# Impedance.net
KiCad netlist of a schematic drawn in EAGLE
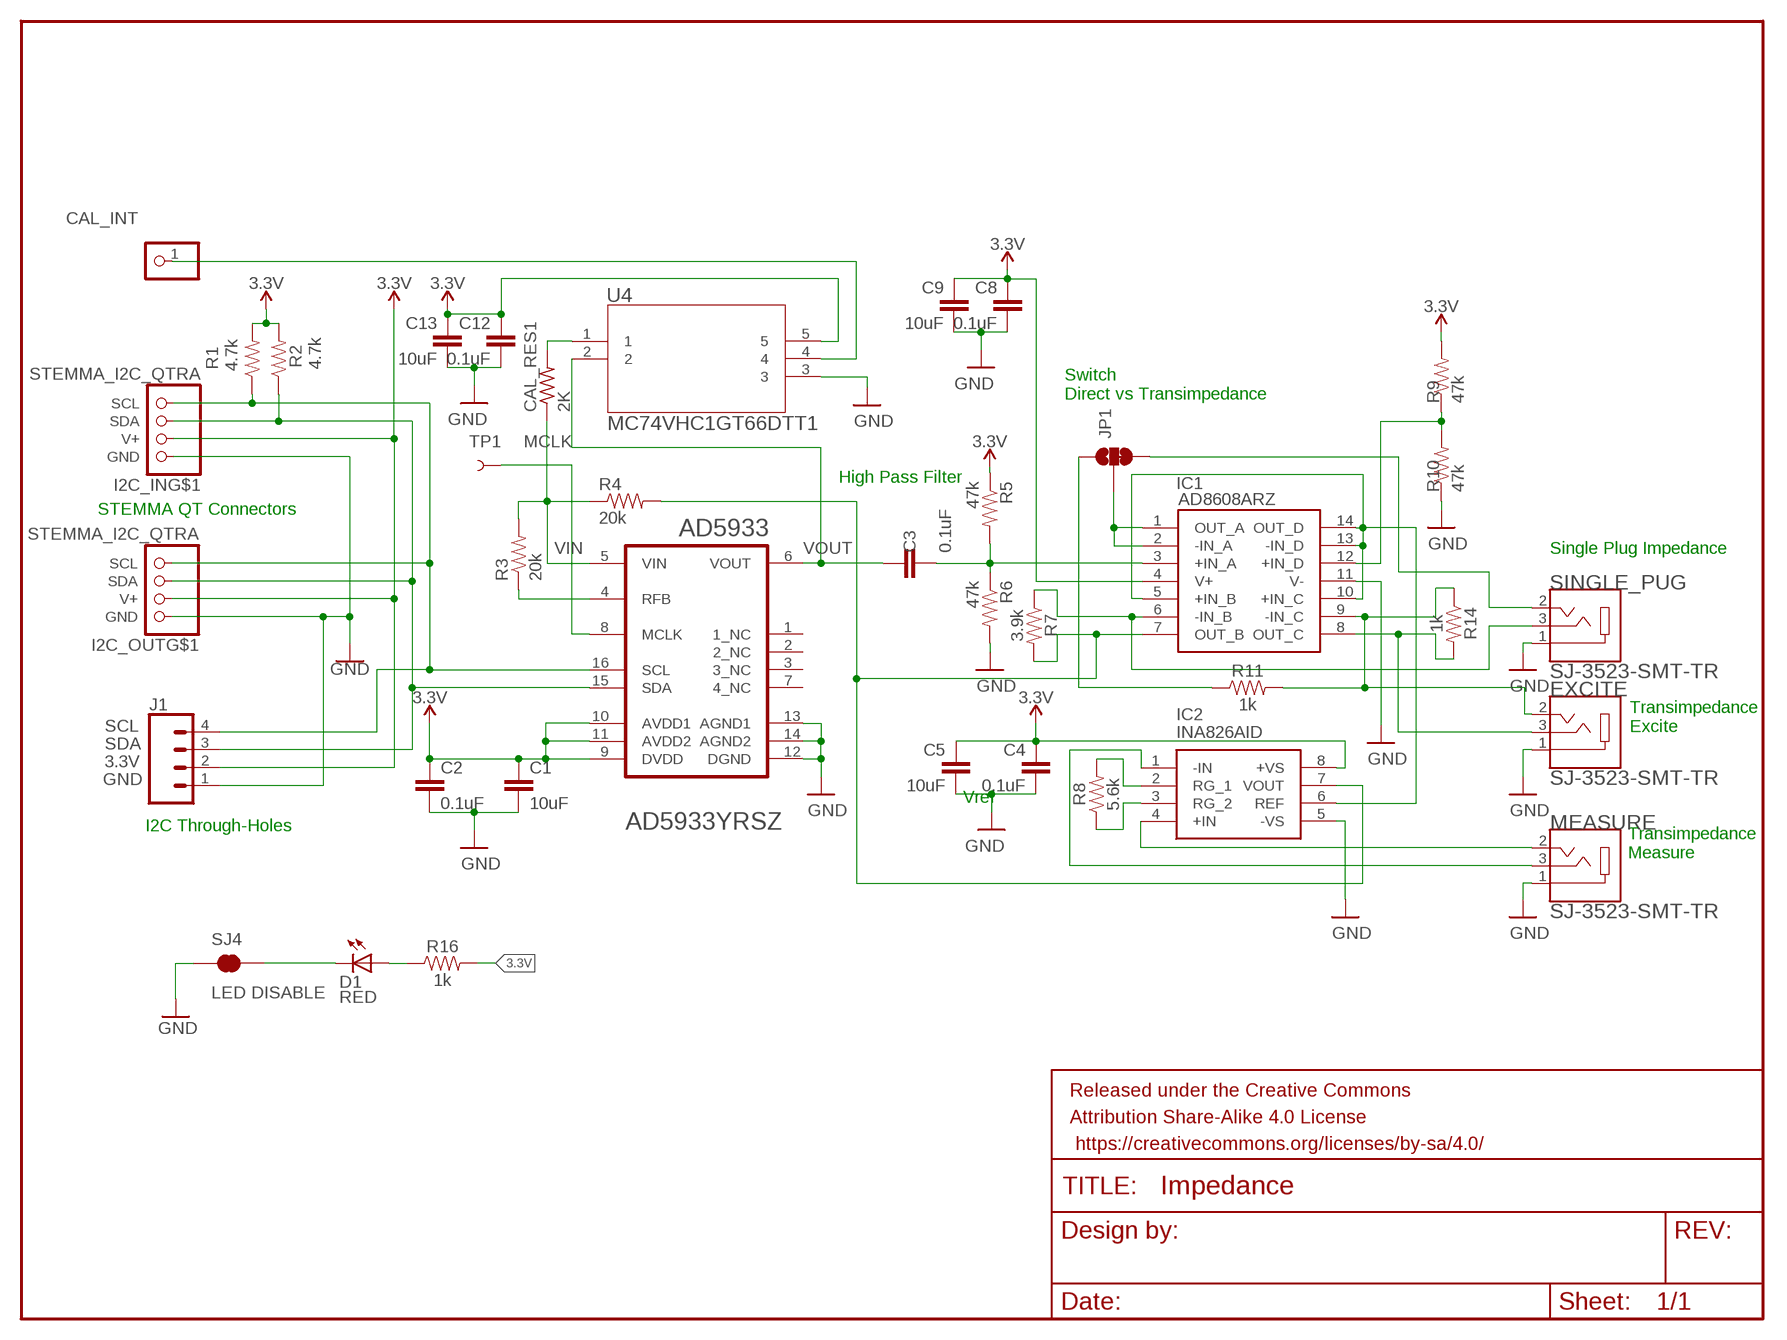
[diagram p0: schematic, sheet 1]

(export (version "E")
  (design (tool "Eeschema 10.0.6"))
  (components
    (comp (ref "AD5933")
      (value "ANALOG_DEVICES_AD5933YRSZANALOG_DEVICES_AD5933YRSZ_0_0")
      (footprint "eagle-import:ANALOG_DEVICES_AD5933YRSZ_0")
      (fields (field (name "MF") "Analog Devices") (field (name "MPN") "AD5933YRSZ"))
      (libsource (lib "eagle-import") (part "ANALOG_DEVICES_AD5933YRSZANALOG_DEVICES_AD5933YRSZ_0_0"))
    )
    (comp (ref "C1")
      (value "10uF")
      (footprint "eagle-import:C0603")
      (libsource (lib "eagle-import") (part "C-EUC0603"))
    )
    (comp (ref "C2")
      (value "0.1uF")
      (footprint "eagle-import:C0603")
      (libsource (lib "eagle-import") (part "C-EUC0603"))
    )
    (comp (ref "C3")
      (value "0.1uF")
      (footprint "eagle-import:0603")
      (libsource (lib "eagle-import") (part "0.1UF-0603-25V-(+80/-20%)"))
    )
    (comp (ref "C4")
      (value "0.1uF")
      (footprint "eagle-import:C0603")
      (libsource (lib "eagle-import") (part "C-EUC0603"))
    )
    (comp (ref "C5")
      (value "10uF")
      (footprint "eagle-import:C0603")
      (libsource (lib "eagle-import") (part "C-EUC0603"))
    )
    (comp (ref "C8")
      (value "0.1uF")
      (footprint "eagle-import:C0603")
      (libsource (lib "eagle-import") (part "C-EUC0603"))
    )
    (comp (ref "C9")
      (value "10uF")
      (footprint "eagle-import:C0603")
      (libsource (lib "eagle-import") (part "C-EUC0603"))
    )
    (comp (ref "C12")
      (value "0.1uF")
      (footprint "eagle-import:C0603")
      (libsource (lib "eagle-import") (part "C-EUC0603"))
    )
    (comp (ref "C13")
      (value "10uF")
      (footprint "eagle-import:C0603")
      (libsource (lib "eagle-import") (part "C-EUC0603"))
    )
    (comp (ref "CAL_INT")
      (value "PINHD-1X1")
      (footprint "eagle-import:1X01")
      (libsource (lib "eagle-import") (part "PINHD-1X1"))
    )
    (comp (ref "CAL_RES1")
      (value "2K")
      (footprint "eagle-import:R0603")
      (libsource (lib "eagle-import") (part "R-US_R0603"))
    )
    (comp (ref "D1")
      (value "RED")
      (footprint "eagle-import:LED-0603")
      (libsource (lib "eagle-import") (part "LED-RED0603"))
    )
    (comp (ref "EXCITE")
      (value "SJ-3523-SMT-TR")
      (footprint "eagle-import:CUI_SJ-3523-SMT-TR")
      (fields (field (name "MF") "CUI Devices"))
      (libsource (lib "eagle-import") (part "SJ-3523-SMT-TR"))
    )
    (comp (ref "FRAME1")
      (value "FRAME-LETTERNO_PACKAGE")
      (footprint "eagle-import:DUMMY")
      (fields (field (name "DESIGNER") "Nobody"))
      (libsource (lib "eagle-import") (part "FRAME-LETTERNO_PACKAGE"))
    )
    (comp (ref "I2C_IN")
      (value "STEMMA_I2C_QTRA")
      (footprint "eagle-import:JST_SH4_RA")
      (libsource (lib "eagle-import") (part "STEMMA_I2C_QTRA"))
    )
    (comp (ref "I2C_OUT")
      (value "STEMMA_I2C_QTRA")
      (footprint "eagle-import:JST_SH4_RA")
      (libsource (lib "eagle-import") (part "STEMMA_I2C_QTRA"))
    )
    (comp (ref "IC1")
      (value "AD8608ARZ")
      (footprint "eagle-import:SOIC127P600X175-14N")
      (fields (field (name "MOUSER_PART_NUMBER") "584-AD8608ARZ"))
      (libsource (lib "eagle-import") (part "AD8608ARZ"))
    )
    (comp (ref "IC2")
      (value "INA826AID")
      (footprint "eagle-import:SOIC127P600X175-8N")
      (fields (field (name "MOUSER_PART_NUMBER") "595-INA826AID"))
      (libsource (lib "eagle-import") (part "INA826AID"))
    )
    (comp (ref "J1")
      (value "CONN_04")
      (footprint "eagle-import:1X04")
      (libsource (lib "eagle-import") (part "CONN_04"))
    )
    (comp (ref "JP1")
      (value "JUMPER-SMT_3_1-NC_TRACE_NO-SILK")
      (footprint "eagle-import:SMT-JUMPER_3_1-NC_TRACE_NO-SILK")
      (libsource (lib "eagle-import") (part "JUMPER-SMT_3_1-NC_TRACE_NO-SILK"))
    )
    (comp (ref "MEASURE")
      (value "SJ-3523-SMT-TR")
      (footprint "eagle-import:CUI_SJ-3523-SMT-TR")
      (fields (field (name "MF") "CUI Devices"))
      (libsource (lib "eagle-import") (part "SJ-3523-SMT-TR"))
    )
    (comp (ref "R1")
      (value "4.7k")
      (footprint "eagle-import:0603")
      (libsource (lib "eagle-import") (part "4.7KOHM-0603-1/10W-1%"))
    )
    (comp (ref "R2")
      (value "4.7k")
      (footprint "eagle-import:0603")
      (libsource (lib "eagle-import") (part "4.7KOHM-0603-1/10W-1%"))
    )
    (comp (ref "R3")
      (value "20k")
      (footprint "eagle-import:0603")
      (libsource (lib "eagle-import") (part "20KOHM-0603-1/10W-1%"))
    )
    (comp (ref "R4")
      (value "20k")
      (footprint "eagle-import:0603")
      (libsource (lib "eagle-import") (part "20KOHM-0603-1/10W-1%"))
    )
    (comp (ref "R5")
      (value "47k")
      (footprint "eagle-import:0603")
      (libsource (lib "eagle-import") (part "47KOHM-0603-1/10W-1%"))
    )
    (comp (ref "R6")
      (value "47k")
      (footprint "eagle-import:0603")
      (libsource (lib "eagle-import") (part "47KOHM-0603-1/10W-1%"))
    )
    (comp (ref "R7")
      (value "3.9k")
      (footprint "eagle-import:0603")
      (libsource (lib "eagle-import") (part "3.9KOHM-0603-1/10W-1%"))
    )
    (comp (ref "R8")
      (value "5.6k")
      (footprint "eagle-import:0603")
      (libsource (lib "eagle-import") (part "5.6KOHM-0603-1/10W-1%"))
    )
    (comp (ref "R9")
      (value "47k")
      (footprint "eagle-import:0603")
      (libsource (lib "eagle-import") (part "47KOHM-0603-1/10W-1%"))
    )
    (comp (ref "R10")
      (value "47k")
      (footprint "eagle-import:0603")
      (libsource (lib "eagle-import") (part "47KOHM-0603-1/10W-1%"))
    )
    (comp (ref "R11")
      (value "1k")
      (footprint "eagle-import:0603")
      (libsource (lib "eagle-import") (part "1KOHM-0603-1/10W-1%"))
    )
    (comp (ref "R14")
      (value "1k")
      (footprint "eagle-import:0603")
      (libsource (lib "eagle-import") (part "1KOHM-0603-1/10W-1%"))
    )
    (comp (ref "R16")
      (value "1k")
      (footprint "eagle-import:0603")
      (libsource (lib "eagle-import") (part "1KOHM-0603-1/10W-1%"))
    )
    (comp (ref "SINGLE_PUG")
      (value "SJ-3523-SMT-TR")
      (footprint "eagle-import:CUI_SJ-3523-SMT-TR")
      (fields (field (name "MF") "CUI Devices"))
      (libsource (lib "eagle-import") (part "SJ-3523-SMT-TR"))
    )
    (comp (ref "SJ4")
      (value "LED DISABLE")
      (footprint "eagle-import:SMT-JUMPER_2_NC_TRACE_NO-SILK")
      (libsource (lib "eagle-import") (part "JUMPER-SMT_2_NC_TRACE_NO-SILK"))
    )
    (comp (ref "TP1")
      (value "TEST-POINT3X5")
      (footprint "eagle-import:PAD.03X.05")
      (libsource (lib "eagle-import") (part "TEST-POINT3X5"))
    )
    (comp (ref "U4")
      (value "MC74VHC1GT66DTT1")
      (footprint "eagle-import:TSOP5_1P65X3P15_ONS")
      (fields (field (name "COPYRIGHT") "Copyright (C) 2024 Ultra Librarian. All rights reserved."))
      (libsource (lib "eagle-import") (part "MC74VHC1GT66DTT1"))
    )
  )
  (nets
    (net (code "1") (name "/MCLK") (class "Default")
      (node (ref "AD5933") (pin "8") (pinfunction "MCLK_8") (pintype "input"))
      (node (ref "TP1") (pin "P$1") (pinfunction "1_P$1") (pintype "bidirectional"))
    )
    (net (code "2") (name "/SCL") (class "Default")
      (node (ref "AD5933") (pin "16") (pinfunction "SCL_16") (pintype "input"))
      (node (ref "I2C_IN") (pin "4") (pinfunction "SCL_4") (pintype "passive"))
      (node (ref "I2C_OUT") (pin "4") (pinfunction "SCL_4") (pintype "passive"))
      (node (ref "J1") (pin "4") (pinfunction "4_4") (pintype "passive"))
      (node (ref "R1") (pin "1") (pinfunction "1_1") (pintype "passive"))
    )
    (net (code "3") (name "/SDA") (class "Default")
      (node (ref "AD5933") (pin "15") (pinfunction "SDA_15") (pintype "bidirectional"))
      (node (ref "I2C_IN") (pin "3") (pinfunction "SDA_3") (pintype "passive"))
      (node (ref "I2C_OUT") (pin "3") (pinfunction "SDA_3") (pintype "passive"))
      (node (ref "J1") (pin "3") (pinfunction "3_3") (pintype "passive"))
      (node (ref "R2") (pin "1") (pinfunction "1_1") (pintype "passive"))
    )
    (net (code "4") (name "/VIN") (class "Default")
      (node (ref "AD5933") (pin "5") (pinfunction "VIN_5") (pintype "input"))
      (node (ref "CAL_RES1") (pin "1") (pinfunction "1_1") (pintype "passive"))
      (node (ref "R3") (pin "2") (pinfunction "2_2") (pintype "passive"))
      (node (ref "R4") (pin "1") (pinfunction "1_1") (pintype "passive"))
    )
    (net (code "5") (name "/VOUT") (class "Default")
      (node (ref "AD5933") (pin "6") (pinfunction "VOUT_6") (pintype "output"))
      (node (ref "C3") (pin "1") (pinfunction "1_1") (pintype "passive"))
      (node (ref "U4") (pin "2") (pinfunction "2_2") (pintype "passive"))
    )
    (net (code "6") (name "3.3V") (class "Default")
      (node (ref "AD5933") (pin "10") (pinfunction "AVDD1_10") (pintype "power_in"))
      (node (ref "AD5933") (pin "11") (pinfunction "AVDD2_11") (pintype "power_in"))
      (node (ref "AD5933") (pin "9") (pinfunction "DVDD_9") (pintype "power_in"))
      (node (ref "C1") (pin "1") (pinfunction "1_1") (pintype "passive"))
      (node (ref "C12") (pin "1") (pinfunction "1_1") (pintype "passive"))
      (node (ref "C13") (pin "1") (pinfunction "1_1") (pintype "passive"))
      (node (ref "C2") (pin "1") (pinfunction "1_1") (pintype "passive"))
      (node (ref "C4") (pin "1") (pinfunction "1_1") (pintype "passive"))
      (node (ref "C5") (pin "1") (pinfunction "1_1") (pintype "passive"))
      (node (ref "C8") (pin "1") (pinfunction "1_1") (pintype "passive"))
      (node (ref "C9") (pin "1") (pinfunction "1_1") (pintype "passive"))
      (node (ref "I2C_IN") (pin "2") (pinfunction "V+_2") (pintype "passive"))
      (node (ref "I2C_OUT") (pin "2") (pinfunction "V+_2") (pintype "passive"))
      (node (ref "IC1") (pin "4") (pinfunction "V+_4") (pintype "power_in"))
      (node (ref "IC2") (pin "8") (pinfunction "+VS_8") (pintype "bidirectional"))
      (node (ref "J1") (pin "2") (pinfunction "2_2") (pintype "passive"))
      (node (ref "R1") (pin "2") (pinfunction "2_2") (pintype "passive"))
      (node (ref "R16") (pin "2") (pinfunction "2_2") (pintype "passive"))
      (node (ref "R2") (pin "2") (pinfunction "2_2") (pintype "passive"))
      (node (ref "R5") (pin "1") (pinfunction "1_1") (pintype "passive"))
      (node (ref "R9") (pin "2") (pinfunction "2_2") (pintype "passive"))
      (node (ref "U4") (pin "5") (pinfunction "5_5") (pintype "passive"))
    )
    (net (code "7") (name "GND") (class "Default")
      (node (ref "AD5933") (pin "12") (pinfunction "DGND_12") (pintype "power_in"))
      (node (ref "AD5933") (pin "13") (pinfunction "AGND1_13") (pintype "power_in"))
      (node (ref "AD5933") (pin "14") (pinfunction "AGND2_14") (pintype "power_in"))
      (node (ref "C1") (pin "2") (pinfunction "2_2") (pintype "passive"))
      (node (ref "C12") (pin "2") (pinfunction "2_2") (pintype "passive"))
      (node (ref "C13") (pin "2") (pinfunction "2_2") (pintype "passive"))
      (node (ref "C2") (pin "2") (pinfunction "2_2") (pintype "passive"))
      (node (ref "C4") (pin "2") (pinfunction "2_2") (pintype "passive"))
      (node (ref "C5") (pin "2") (pinfunction "2_2") (pintype "passive"))
      (node (ref "C8") (pin "2") (pinfunction "2_2") (pintype "passive"))
      (node (ref "C9") (pin "2") (pinfunction "2_2") (pintype "passive"))
      (node (ref "EXCITE") (pin "1") (pinfunction "1_1") (pintype "passive"))
      (node (ref "I2C_IN") (pin "1") (pinfunction "GND_1") (pintype "passive"))
      (node (ref "I2C_OUT") (pin "1") (pinfunction "GND_1") (pintype "passive"))
      (node (ref "IC1") (pin "11") (pinfunction "V-_11") (pintype "power_in"))
      (node (ref "IC2") (pin "5") (pinfunction "-VS_5") (pintype "bidirectional"))
      (node (ref "J1") (pin "1") (pinfunction "1_1") (pintype "passive"))
      (node (ref "MEASURE") (pin "1") (pinfunction "1_1") (pintype "passive"))
      (node (ref "R10") (pin "1") (pinfunction "1_1") (pintype "passive"))
      (node (ref "R6") (pin "2") (pinfunction "2_2") (pintype "passive"))
      (node (ref "SINGLE_PUG") (pin "1") (pinfunction "1_1") (pintype "passive"))
      (node (ref "SJ4") (pin "1") (pinfunction "1_1") (pintype "passive"))
      (node (ref "U4") (pin "3") (pinfunction "3_3") (pintype "passive"))
    )
    (net (code "8") (name "Net-(AD5933-RFB)") (class "Default")
      (node (ref "AD5933") (pin "4") (pinfunction "RFB_4") (pintype "input"))
      (node (ref "R3") (pin "1") (pinfunction "1_1") (pintype "passive"))
    )
    (net (code "9") (name "Net-(CAL_INT-Pad1)") (class "Default")
      (node (ref "CAL_INT") (pin "1") (pinfunction "1_1") (pintype "passive"))
      (node (ref "U4") (pin "4") (pinfunction "4_4") (pintype "passive"))
    )
    (net (code "10") (name "Net-(CAL_RES1-Pad2)") (class "Default")
      (node (ref "CAL_RES1") (pin "2") (pinfunction "2_2") (pintype "passive"))
      (node (ref "U4") (pin "1") (pinfunction "1_1") (pintype "passive"))
    )
    (net (code "11") (name "Net-(D1-PadA)") (class "Default")
      (node (ref "D1") (pin "A") (pinfunction "A_A") (pintype "passive"))
      (node (ref "R16") (pin "1") (pinfunction "1_1") (pintype "passive"))
    )
    (net (code "12") (name "Net-(D1-PadC)") (class "Default")
      (node (ref "D1") (pin "C") (pinfunction "C_C") (pintype "passive"))
      (node (ref "SJ4") (pin "2") (pinfunction "2_2") (pintype "passive"))
    )
    (net (code "13") (name "Net-(IC1-+IN_A)") (class "Default")
      (node (ref "C3") (pin "2") (pinfunction "2_2") (pintype "passive"))
      (node (ref "IC1") (pin "3") (pinfunction "+IN_A_3") (pintype "input"))
      (node (ref "R5") (pin "2") (pinfunction "2_2") (pintype "passive"))
      (node (ref "R6") (pin "1") (pinfunction "1_1") (pintype "passive"))
    )
    (net (code "14") (name "Net-(IC1-+IN_B)") (class "Default")
      (node (ref "IC1") (pin "10") (pinfunction "+IN_C_10") (pintype "input"))
      (node (ref "IC1") (pin "13") (pinfunction "-IN_D_13") (pintype "input"))
      (node (ref "IC1") (pin "14") (pinfunction "OUT_D_14") (pintype "output"))
      (node (ref "IC1") (pin "5") (pinfunction "+IN_B_5") (pintype "input"))
      (node (ref "IC2") (pin "6") (pinfunction "REF_6") (pintype "bidirectional"))
    )
    (net (code "15") (name "Net-(IC1-+IN_D)") (class "Default")
      (node (ref "IC1") (pin "12") (pinfunction "+IN_D_12") (pintype "input"))
      (node (ref "R10") (pin "2") (pinfunction "2_2") (pintype "passive"))
      (node (ref "R9") (pin "1") (pinfunction "1_1") (pintype "passive"))
    )
    (net (code "16") (name "Net-(IC1--IN_A)") (class "Default")
      (node (ref "IC1") (pin "1") (pinfunction "OUT_A_1") (pintype "output"))
      (node (ref "IC1") (pin "2") (pinfunction "-IN_A_2") (pintype "input"))
      (node (ref "JP1") (pin "2") (pinfunction "2_2") (pintype "passive"))
    )
    (net (code "17") (name "Net-(IC1--IN_B)") (class "Default")
      (node (ref "IC1") (pin "6") (pinfunction "-IN_B_6") (pintype "input"))
      (node (ref "R7") (pin "1") (pinfunction "1_1") (pintype "passive"))
      (node (ref "SINGLE_PUG") (pin "3") (pinfunction "3_3") (pintype "passive"))
    )
    (net (code "18") (name "Net-(IC1--IN_C)") (class "Default")
      (node (ref "EXCITE") (pin "2") (pinfunction "2_2") (pintype "passive"))
      (node (ref "IC1") (pin "9") (pinfunction "-IN_C_9") (pintype "input"))
      (node (ref "R11") (pin "2") (pinfunction "2_2") (pintype "passive"))
      (node (ref "R14") (pin "1") (pinfunction "1_1") (pintype "passive"))
    )
    (net (code "19") (name "Net-(IC1-OUT_B)") (class "Default")
      (node (ref "IC1") (pin "7") (pinfunction "OUT_B_7") (pintype "output"))
      (node (ref "IC2") (pin "7") (pinfunction "VOUT_7") (pintype "bidirectional"))
      (node (ref "R4") (pin "2") (pinfunction "2_2") (pintype "passive"))
      (node (ref "R7") (pin "2") (pinfunction "2_2") (pintype "passive"))
    )
    (net (code "20") (name "Net-(IC1-OUT_C)") (class "Default")
      (node (ref "EXCITE") (pin "3") (pinfunction "3_3") (pintype "passive"))
      (node (ref "IC1") (pin "8") (pinfunction "OUT_C_8") (pintype "output"))
      (node (ref "R14") (pin "2") (pinfunction "2_2") (pintype "passive"))
    )
    (net (code "21") (name "Net-(IC2-+IN)") (class "Default")
      (node (ref "IC2") (pin "4") (pinfunction "+IN_4") (pintype "bidirectional"))
      (node (ref "MEASURE") (pin "2") (pinfunction "2_2") (pintype "passive"))
    )
    (net (code "22") (name "Net-(IC2--IN)") (class "Default")
      (node (ref "IC2") (pin "1") (pinfunction "-IN_1") (pintype "bidirectional"))
      (node (ref "MEASURE") (pin "3") (pinfunction "3_3") (pintype "passive"))
    )
    (net (code "23") (name "Net-(IC2-RG_1)") (class "Default")
      (node (ref "IC2") (pin "2") (pinfunction "RG_1_2") (pintype "bidirectional"))
      (node (ref "R8") (pin "2") (pinfunction "2_2") (pintype "passive"))
    )
    (net (code "24") (name "Net-(IC2-RG_2)") (class "Default")
      (node (ref "IC2") (pin "3") (pinfunction "RG_2_3") (pintype "bidirectional"))
      (node (ref "R8") (pin "1") (pinfunction "1_1") (pintype "passive"))
    )
    (net (code "25") (name "Net-(JP1-Pad1)") (class "Default")
      (node (ref "JP1") (pin "1") (pinfunction "1_1") (pintype "passive"))
      (node (ref "R11") (pin "1") (pinfunction "1_1") (pintype "passive"))
    )
    (net (code "26") (name "Net-(JP1-Pad3)") (class "Default")
      (node (ref "JP1") (pin "3") (pinfunction "3_3") (pintype "passive"))
      (node (ref "SINGLE_PUG") (pin "2") (pinfunction "2_2") (pintype "passive"))
    )
    (net (code "27") (name "unconnected-(AD5933-1_NC-Pad1)") (class "Default")
      (node (ref "AD5933") (pin "1") (pinfunction "1_NC_1") (pintype "passive"))
    )
    (net (code "28") (name "unconnected-(AD5933-2_NC-Pad2)") (class "Default")
      (node (ref "AD5933") (pin "2") (pinfunction "2_NC_2") (pintype "passive"))
    )
    (net (code "29") (name "unconnected-(AD5933-3_NC-Pad3)") (class "Default")
      (node (ref "AD5933") (pin "3") (pinfunction "3_NC_3") (pintype "passive"))
    )
    (net (code "30") (name "unconnected-(AD5933-4_NC-Pad7)") (class "Default")
      (node (ref "AD5933") (pin "7") (pinfunction "4_NC_7") (pintype "passive"))
    )
  )
)
